# PCB_Design.net
KiCad netlist of a schematic drawn in EAGLE
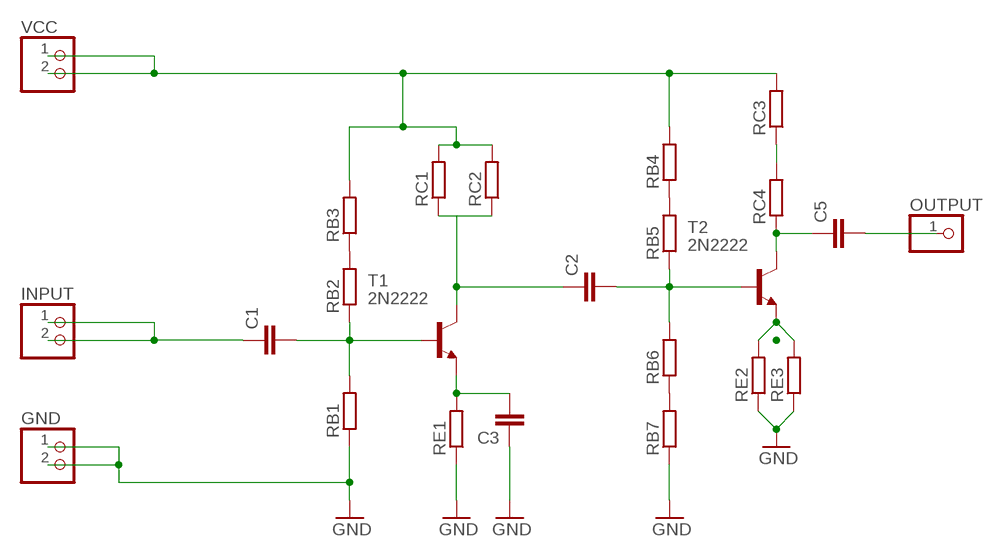
[diagram p0: schematic, sheet 1]

(export (version "E")
  (design (tool "Eeschema 10.0.6"))
  (components
    (comp (ref "C1")
      (value "C-EU025-025X050")
      (footprint "eagle-import:C025-025X050")
      (libsource (lib "eagle-import") (part "C-EU025-025X050"))
    )
    (comp (ref "C2")
      (value "C-EU025-025X050")
      (footprint "eagle-import:C025-025X050")
      (libsource (lib "eagle-import") (part "C-EU025-025X050"))
    )
    (comp (ref "C3")
      (value "C-EU025-025X050")
      (footprint "eagle-import:C025-025X050")
      (libsource (lib "eagle-import") (part "C-EU025-025X050"))
    )
    (comp (ref "C5")
      (value "C-EU025-025X050")
      (footprint "eagle-import:C025-025X050")
      (libsource (lib "eagle-import") (part "C-EU025-025X050"))
    )
    (comp (ref "GND")
      (value "PINHD-1X2")
      (footprint "eagle-import:1X02")
      (libsource (lib "eagle-import") (part "PINHD-1X2"))
    )
    (comp (ref "INPUT")
      (value "PINHD-1X2")
      (footprint "eagle-import:1X02")
      (libsource (lib "eagle-import") (part "PINHD-1X2"))
    )
    (comp (ref "OUTPUT")
      (value "PINHD-1X1")
      (footprint "eagle-import:1X01")
      (libsource (lib "eagle-import") (part "PINHD-1X1"))
    )
    (comp (ref "RB1")
      (value "R-EU_0204/7")
      (footprint "eagle-import:0204_7")
      (libsource (lib "eagle-import") (part "R-EU_0204/7"))
    )
    (comp (ref "RB2")
      (value "R-EU_0204/7")
      (footprint "eagle-import:0204_7")
      (libsource (lib "eagle-import") (part "R-EU_0204/7"))
    )
    (comp (ref "RB3")
      (value "R-EU_0204/7")
      (footprint "eagle-import:0204_7")
      (libsource (lib "eagle-import") (part "R-EU_0204/7"))
    )
    (comp (ref "RB4")
      (value "R-EU_0204/7")
      (footprint "eagle-import:0204_7")
      (libsource (lib "eagle-import") (part "R-EU_0204/7"))
    )
    (comp (ref "RB5")
      (value "R-EU_0204/7")
      (footprint "eagle-import:0204_7")
      (libsource (lib "eagle-import") (part "R-EU_0204/7"))
    )
    (comp (ref "RB6")
      (value "R-EU_0204/7")
      (footprint "eagle-import:0204_7")
      (libsource (lib "eagle-import") (part "R-EU_0204/7"))
    )
    (comp (ref "RB7")
      (value "R-EU_0204/7")
      (footprint "eagle-import:0204_7")
      (libsource (lib "eagle-import") (part "R-EU_0204/7"))
    )
    (comp (ref "RC1")
      (value "R-EU_0204/7")
      (footprint "eagle-import:0204_7")
      (libsource (lib "eagle-import") (part "R-EU_0204/7"))
    )
    (comp (ref "RC2")
      (value "R-EU_0204/7")
      (footprint "eagle-import:0204_7")
      (libsource (lib "eagle-import") (part "R-EU_0204/7"))
    )
    (comp (ref "RC3")
      (value "R-EU_0204/7")
      (footprint "eagle-import:0204_7")
      (libsource (lib "eagle-import") (part "R-EU_0204/7"))
    )
    (comp (ref "RC4")
      (value "R-EU_0204/7")
      (footprint "eagle-import:0204_7")
      (libsource (lib "eagle-import") (part "R-EU_0204/7"))
    )
    (comp (ref "RE1")
      (value "R-EU_0204/7")
      (footprint "eagle-import:0204_7")
      (libsource (lib "eagle-import") (part "R-EU_0204/7"))
    )
    (comp (ref "RE2")
      (value "R-EU_0204/7")
      (footprint "eagle-import:0204_7")
      (libsource (lib "eagle-import") (part "R-EU_0204/7"))
    )
    (comp (ref "RE3")
      (value "R-EU_0204/7")
      (footprint "eagle-import:0204_7")
      (libsource (lib "eagle-import") (part "R-EU_0204/7"))
    )
    (comp (ref "T1")
      (value "2N2222")
      (footprint "eagle-import:TO18")
      (libsource (lib "eagle-import") (part "2N2222"))
    )
    (comp (ref "T2")
      (value "2N2222")
      (footprint "eagle-import:TO18")
      (libsource (lib "eagle-import") (part "2N2222"))
    )
    (comp (ref "VCC")
      (value "PINHD-1X2")
      (footprint "eagle-import:1X02")
      (libsource (lib "eagle-import") (part "PINHD-1X2"))
    )
  )
  (nets
    (net (code "1") (name "GND") (class "Default")
      (node (ref "C3") (pin "1") (pinfunction "1_1") (pintype "passive"))
      (node (ref "GND") (pin "1") (pinfunction "1_1") (pintype "passive"))
      (node (ref "GND") (pin "2") (pinfunction "2_2") (pintype "passive"))
      (node (ref "RB1") (pin "1") (pinfunction "1_1") (pintype "passive"))
      (node (ref "RB7") (pin "1") (pinfunction "1_1") (pintype "passive"))
      (node (ref "RE1") (pin "1") (pinfunction "1_1") (pintype "passive"))
      (node (ref "RE2") (pin "1") (pinfunction "1_1") (pintype "passive"))
      (node (ref "RE3") (pin "1") (pinfunction "1_1") (pintype "passive"))
    )
    (net (code "2") (name "Net-(C1-Pad1)") (class "Default")
      (node (ref "C1") (pin "1") (pinfunction "1_1") (pintype "passive"))
      (node (ref "INPUT") (pin "1") (pinfunction "1_1") (pintype "passive"))
      (node (ref "INPUT") (pin "2") (pinfunction "2_2") (pintype "passive"))
    )
    (net (code "3") (name "Net-(C5-Pad2)") (class "Default")
      (node (ref "C5") (pin "2") (pinfunction "2_2") (pintype "passive"))
      (node (ref "OUTPUT") (pin "1") (pinfunction "1_1") (pintype "passive"))
    )
    (net (code "4") (name "Net-(RB2-Pad2)") (class "Default")
      (node (ref "RB2") (pin "2") (pinfunction "2_2") (pintype "passive"))
      (node (ref "RB3") (pin "1") (pinfunction "1_1") (pintype "passive"))
    )
    (net (code "5") (name "Net-(RB3-Pad2)") (class "Default")
      (node (ref "RB3") (pin "2") (pinfunction "2_2") (pintype "passive"))
      (node (ref "RB4") (pin "2") (pinfunction "2_2") (pintype "passive"))
      (node (ref "RC1") (pin "2") (pinfunction "2_2") (pintype "passive"))
      (node (ref "RC2") (pin "2") (pinfunction "2_2") (pintype "passive"))
      (node (ref "RC3") (pin "2") (pinfunction "2_2") (pintype "passive"))
      (node (ref "VCC") (pin "1") (pinfunction "1_1") (pintype "passive"))
      (node (ref "VCC") (pin "2") (pinfunction "2_2") (pintype "passive"))
    )
    (net (code "6") (name "Net-(RB4-Pad1)") (class "Default")
      (node (ref "RB4") (pin "1") (pinfunction "1_1") (pintype "passive"))
      (node (ref "RB5") (pin "2") (pinfunction "2_2") (pintype "passive"))
    )
    (net (code "7") (name "Net-(RB6-Pad1)") (class "Default")
      (node (ref "RB6") (pin "1") (pinfunction "1_1") (pintype "passive"))
      (node (ref "RB7") (pin "2") (pinfunction "2_2") (pintype "passive"))
    )
    (net (code "8") (name "Net-(RC3-Pad1)") (class "Default")
      (node (ref "RC3") (pin "1") (pinfunction "1_1") (pintype "passive"))
      (node (ref "RC4") (pin "2") (pinfunction "2_2") (pintype "passive"))
    )
    (net (code "9") (name "Net-(T1-B)") (class "Default")
      (node (ref "C1") (pin "2") (pinfunction "2_2") (pintype "passive"))
      (node (ref "RB1") (pin "2") (pinfunction "2_2") (pintype "passive"))
      (node (ref "RB2") (pin "1") (pinfunction "1_1") (pintype "passive"))
      (node (ref "T1") (pin "2") (pinfunction "B_2") (pintype "passive"))
    )
    (net (code "10") (name "Net-(T1-C)") (class "Default")
      (node (ref "C2") (pin "1") (pinfunction "1_1") (pintype "passive"))
      (node (ref "RC1") (pin "1") (pinfunction "1_1") (pintype "passive"))
      (node (ref "RC2") (pin "1") (pinfunction "1_1") (pintype "passive"))
      (node (ref "T1") (pin "3") (pinfunction "C_3") (pintype "passive"))
    )
    (net (code "11") (name "Net-(T1-E)") (class "Default")
      (node (ref "C3") (pin "2") (pinfunction "2_2") (pintype "passive"))
      (node (ref "RE1") (pin "2") (pinfunction "2_2") (pintype "passive"))
      (node (ref "T1") (pin "1") (pinfunction "E_1") (pintype "passive"))
    )
    (net (code "12") (name "Net-(T2-B)") (class "Default")
      (node (ref "C2") (pin "2") (pinfunction "2_2") (pintype "passive"))
      (node (ref "RB5") (pin "1") (pinfunction "1_1") (pintype "passive"))
      (node (ref "RB6") (pin "2") (pinfunction "2_2") (pintype "passive"))
      (node (ref "T2") (pin "2") (pinfunction "B_2") (pintype "passive"))
    )
    (net (code "13") (name "Net-(T2-C)") (class "Default")
      (node (ref "C5") (pin "1") (pinfunction "1_1") (pintype "passive"))
      (node (ref "RC4") (pin "1") (pinfunction "1_1") (pintype "passive"))
      (node (ref "T2") (pin "3") (pinfunction "C_3") (pintype "passive"))
    )
    (net (code "14") (name "Net-(T2-E)") (class "Default")
      (node (ref "RE2") (pin "2") (pinfunction "2_2") (pintype "passive"))
      (node (ref "RE3") (pin "2") (pinfunction "2_2") (pintype "passive"))
      (node (ref "T2") (pin "1") (pinfunction "E_1") (pintype "passive"))
    )
  )
)
